# Connectors.net
KiCad netlist of a schematic drawn in Altium Designer
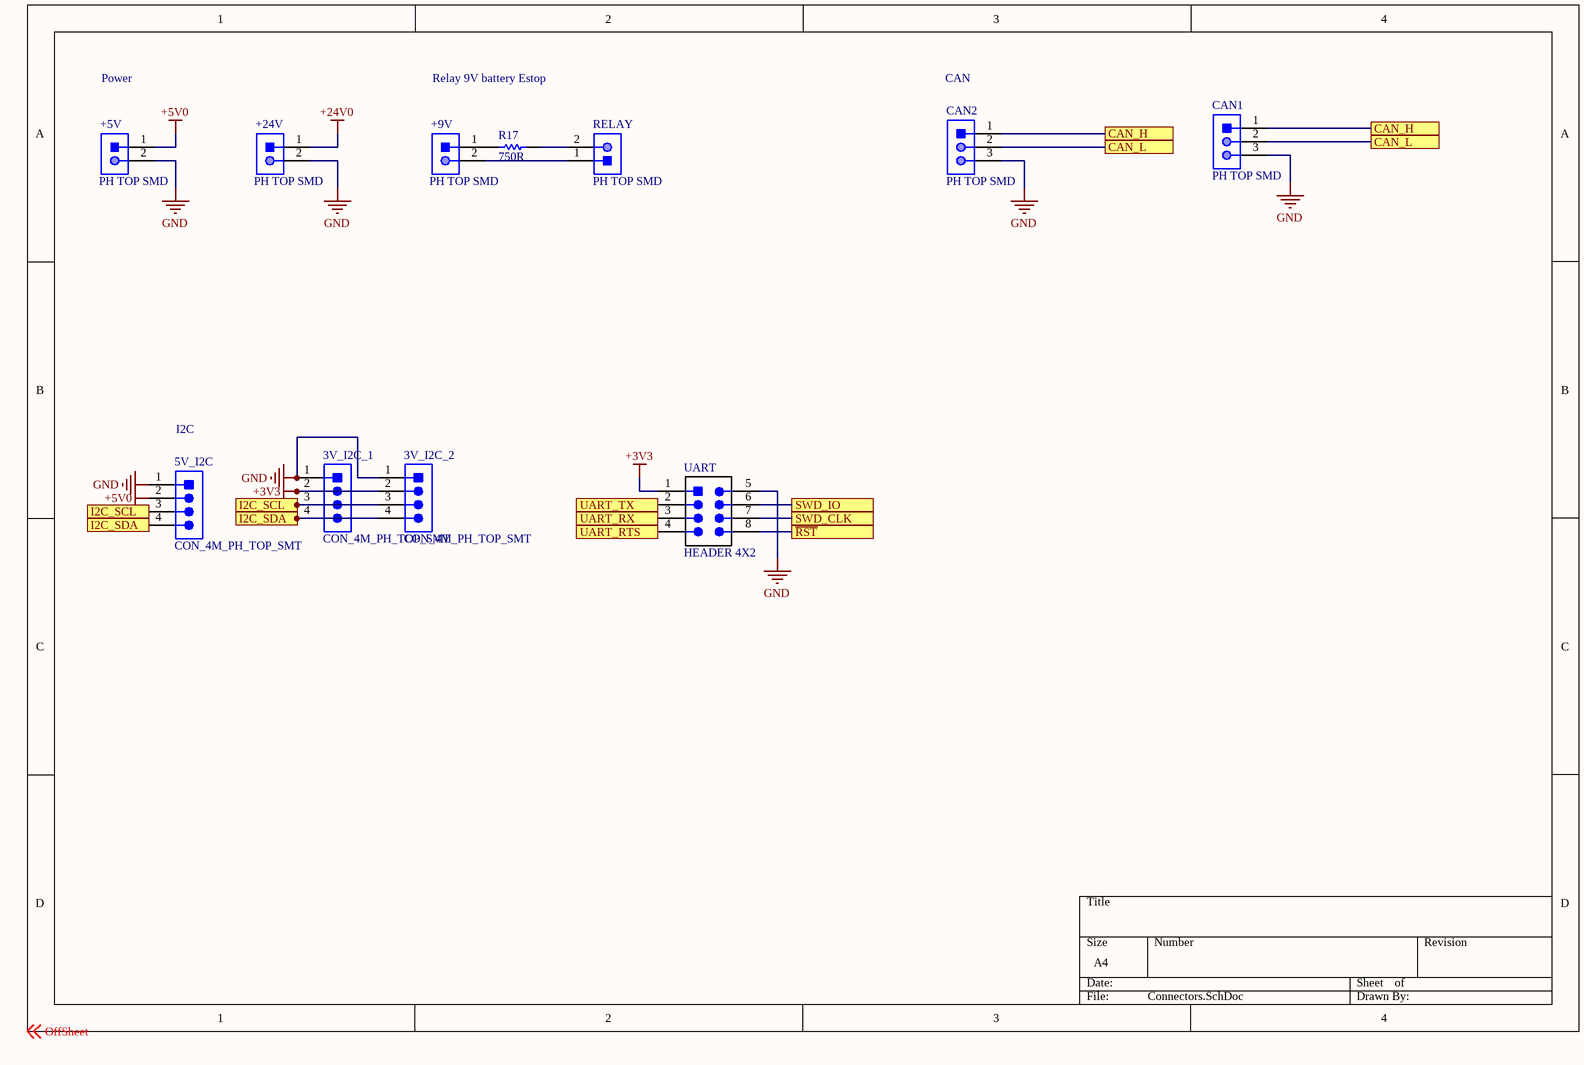
[diagram p0: Connectors.SchDoc]

(export (version "E")
  (design (tool "Eeschema 10.0.6"))
  (components
    (comp (ref "+5V")
      (value "PH TOP SMD")
      (footprint "JST-B2B-SM4-TB")
      (description "CONN HEADER PH TOP 2POS 2MM SMD")
      (fields (field (name "MANUFACTURER") "JST") (field (name "PART NUMBER") "B2B-PH-SM4-TB"))
      (libsource (lib "UWRT_Schematic_Library_2019") (part "CON_2M_PH_TOP_SMT"))
    )
    (comp (ref "+9V")
      (value "PH TOP SMD")
      (footprint "JST-B2B-SM4-TB")
      (description "CONN HEADER PH TOP 2POS 2MM SMD")
      (fields (field (name "MANUFACTURER") "JST") (field (name "PART NUMBER") "B2B-PH-SM4-TB"))
      (libsource (lib "UWRT_Schematic_Library_2019") (part "CON_2M_PH_TOP_SMT"))
    )
    (comp (ref "+24V")
      (value "PH TOP SMD")
      (footprint "JST-B2B-SM4-TB")
      (description "CONN HEADER PH TOP 2POS 2MM SMD")
      (fields (field (name "MANUFACTURER") "JST") (field (name "PART NUMBER") "B2B-PH-SM4-TB"))
      (libsource (lib "UWRT_Schematic_Library_2019") (part "CON_2M_PH_TOP_SMT"))
    )
    (comp (ref "3V_I2C_1")
      (value "CON_4M_PH_TOP_SMT")
      (footprint "JST-B4B-SM4-TB")
      (description "CONN HEADER PH TOP 4POS 2MM SMD")
      (fields (field (name "MANUFACTURER") "JST") (field (name "MPN") "B4B-PH-SM4-TB(LF)(SN)"))
      (libsource (lib "UWRT_Schematic_Library_2019") (part "CON_4M_PH_TOP_SMT"))
    )
    (comp (ref "3V_I2C_2")
      (value "CON_4M_PH_TOP_SMT")
      (footprint "JST-B4B-SM4-TB")
      (description "CONN HEADER PH TOP 4POS 2MM SMD")
      (fields (field (name "MANUFACTURER") "JST") (field (name "MPN") "B4B-PH-SM4-TB(LF)(SN)"))
      (libsource (lib "UWRT_Schematic_Library_2019") (part "CON_4M_PH_TOP_SMT"))
    )
    (comp (ref "5V_I2C")
      (value "CON_4M_PH_TOP_SMT")
      (footprint "JST-B4B-SM4-TB")
      (description "CONN HEADER PH TOP 4POS 2MM SMD")
      (fields (field (name "MANUFACTURER") "JST") (field (name "MPN") "B4B-PH-SM4-TB(LF)(SN)"))
      (libsource (lib "UWRT_Schematic_Library_2019") (part "CON_4M_PH_TOP_SMT"))
    )
    (comp (ref "CAN1")
      (value "PH TOP SMD")
      (footprint "JST-B3B-SM4-TB")
      (description "CONN HEADER PH TOP 3POS 2MM SMD")
      (fields (field (name "MANUFACTURER") "JST") (field (name "PART NUMBER") "B3B-PH-SM4-TB"))
      (libsource (lib "UWRT_Schematic_Library_2019") (part "CON_3M_PH_TOP_SMT"))
    )
    (comp (ref "CAN2")
      (value "PH TOP SMD")
      (footprint "JST-B3B-SM4-TB")
      (description "CONN HEADER PH TOP 3POS 2MM SMD")
      (fields (field (name "MANUFACTURER") "JST") (field (name "PART NUMBER") "B3B-PH-SM4-TB"))
      (libsource (lib "UWRT_Schematic_Library_2019") (part "CON_3M_PH_TOP_SMT"))
    )
    (comp (ref "R17")
      (value "750R")
      (footprint "RESC0603(1608)_N")
      (description "RES SMD 750 OHM 0.5% 1/10W 0603")
      (fields (field (name "MANUFACTURER") "Yageo") (field (name "MPN") "RC0603JR-07750RL"))
      (libsource (lib "UWRT_Schematic_Library_2019") (part "RES_750R_0603"))
    )
    (comp (ref "RELAY")
      (value "PH TOP SMD")
      (footprint "JST-B2B-SM4-TB")
      (description "CONN HEADER PH TOP 2POS 2MM SMD")
      (fields (field (name "MANUFACTURER") "JST") (field (name "PART NUMBER") "B2B-PH-SM4-TB"))
      (libsource (lib "") (part "CON_2M_PH_TOP_SMT_1"))
    )
    (comp (ref "UART")
      (value "HEADER 4X2")
      (footprint "UWRT_Footprint_Library_2019:HEADER_2X4")
      (description "Header, 4-Pin Dual row")
      (fields (field (name "PUBLISHER") "Altium Limited"))
      (libsource (lib "UWRT_Schematic_Library_2019") (part "HEADER 4X2"))
    )
  )
  (nets
    (net (code "1") (name "+3V3") (class "Default")
      (node (ref "3V_I2C_1") (pin "2") (pinfunction "2_2") (pintype "passive"))
      (node (ref "3V_I2C_2") (pin "2") (pinfunction "2_2") (pintype "passive"))
      (node (ref "UART") (pin "1") (pinfunction "VCC_1") (pintype "passive"))
    )
    (net (code "2") (name "+5V0") (class "Default")
      (node (ref "+5V") (pin "1") (pinfunction "1_1") (pintype "passive"))
      (node (ref "5V_I2C") (pin "2") (pinfunction "2_2") (pintype "passive"))
    )
    (net (code "3") (name "+24V0") (class "Default")
      (node (ref "+24V") (pin "1") (pinfunction "1_1") (pintype "passive"))
    )
    (net (code "4") (name "/CAN_H") (class "Default")
      (node (ref "CAN1") (pin "1") (pinfunction "1_1") (pintype "passive"))
      (node (ref "CAN2") (pin "1") (pinfunction "1_1") (pintype "passive"))
    )
    (net (code "5") (name "/CAN_L") (class "Default")
      (node (ref "CAN1") (pin "2") (pinfunction "2_2") (pintype "passive"))
      (node (ref "CAN2") (pin "2") (pinfunction "2_2") (pintype "passive"))
    )
    (net (code "6") (name "/I2C_SCL") (class "Default")
      (node (ref "3V_I2C_1") (pin "3") (pinfunction "3_3") (pintype "passive"))
      (node (ref "3V_I2C_2") (pin "3") (pinfunction "3_3") (pintype "passive"))
      (node (ref "5V_I2C") (pin "3") (pinfunction "3_3") (pintype "passive"))
    )
    (net (code "7") (name "/I2C_SDA") (class "Default")
      (node (ref "3V_I2C_1") (pin "4") (pinfunction "4_4") (pintype "passive"))
      (node (ref "3V_I2C_2") (pin "4") (pinfunction "4_4") (pintype "passive"))
      (node (ref "5V_I2C") (pin "4") (pinfunction "4_4") (pintype "passive"))
    )
    (net (code "8") (name "/SWD_CLK") (class "Default")
      (node (ref "UART") (pin "7") (pinfunction "3_7") (pintype "passive"))
    )
    (net (code "9") (name "/SWD_IO") (class "Default")
      (node (ref "UART") (pin "6") (pinfunction "2_6") (pintype "passive"))
    )
    (net (code "10") (name "/UART_RTS") (class "Default")
      (node (ref "UART") (pin "4") (pinfunction "4_4") (pintype "passive"))
    )
    (net (code "11") (name "/UART_RX") (class "Default")
      (node (ref "UART") (pin "3") (pinfunction "3_3") (pintype "passive"))
    )
    (net (code "12") (name "/UART_TX") (class "Default")
      (node (ref "UART") (pin "2") (pinfunction "2_2") (pintype "passive"))
    )
    (net (code "13") (name "/~{RST}") (class "Default")
      (node (ref "UART") (pin "8") (pinfunction "4_8") (pintype "passive"))
    )
    (net (code "14") (name "GND") (class "Default")
      (node (ref "+24V") (pin "2") (pinfunction "2_2") (pintype "passive"))
      (node (ref "+5V") (pin "2") (pinfunction "2_2") (pintype "passive"))
      (node (ref "3V_I2C_1") (pin "1") (pinfunction "1_1") (pintype "passive"))
      (node (ref "3V_I2C_2") (pin "1") (pinfunction "1_1") (pintype "passive"))
      (node (ref "5V_I2C") (pin "1") (pinfunction "1_1") (pintype "passive"))
      (node (ref "CAN1") (pin "3") (pinfunction "3_3") (pintype "passive"))
      (node (ref "CAN2") (pin "3") (pinfunction "3_3") (pintype "passive"))
      (node (ref "UART") (pin "5") (pinfunction "GND_5") (pintype "passive"))
    )
    (net (code "15") (name "Net-(+9V-Pad1)") (class "Default")
      (node (ref "+9V") (pin "1") (pinfunction "1_1") (pintype "passive"))
      (node (ref "R17") (pin "1") (pinfunction "1_1") (pintype "passive"))
    )
    (net (code "16") (name "Net-(+9V-Pad2)") (class "Default")
      (node (ref "+9V") (pin "2") (pinfunction "2_2") (pintype "passive"))
      (node (ref "RELAY") (pin "1") (pinfunction "1_1") (pintype "passive"))
    )
    (net (code "17") (name "Net-(R17-Pad2)") (class "Default")
      (node (ref "R17") (pin "2") (pinfunction "2_2") (pintype "passive"))
      (node (ref "RELAY") (pin "2") (pinfunction "2_2") (pintype "passive"))
    )
  )
)
